# 06-USB3_PCIe.net
KiCad netlist of a schematic drawn in Altium Designer
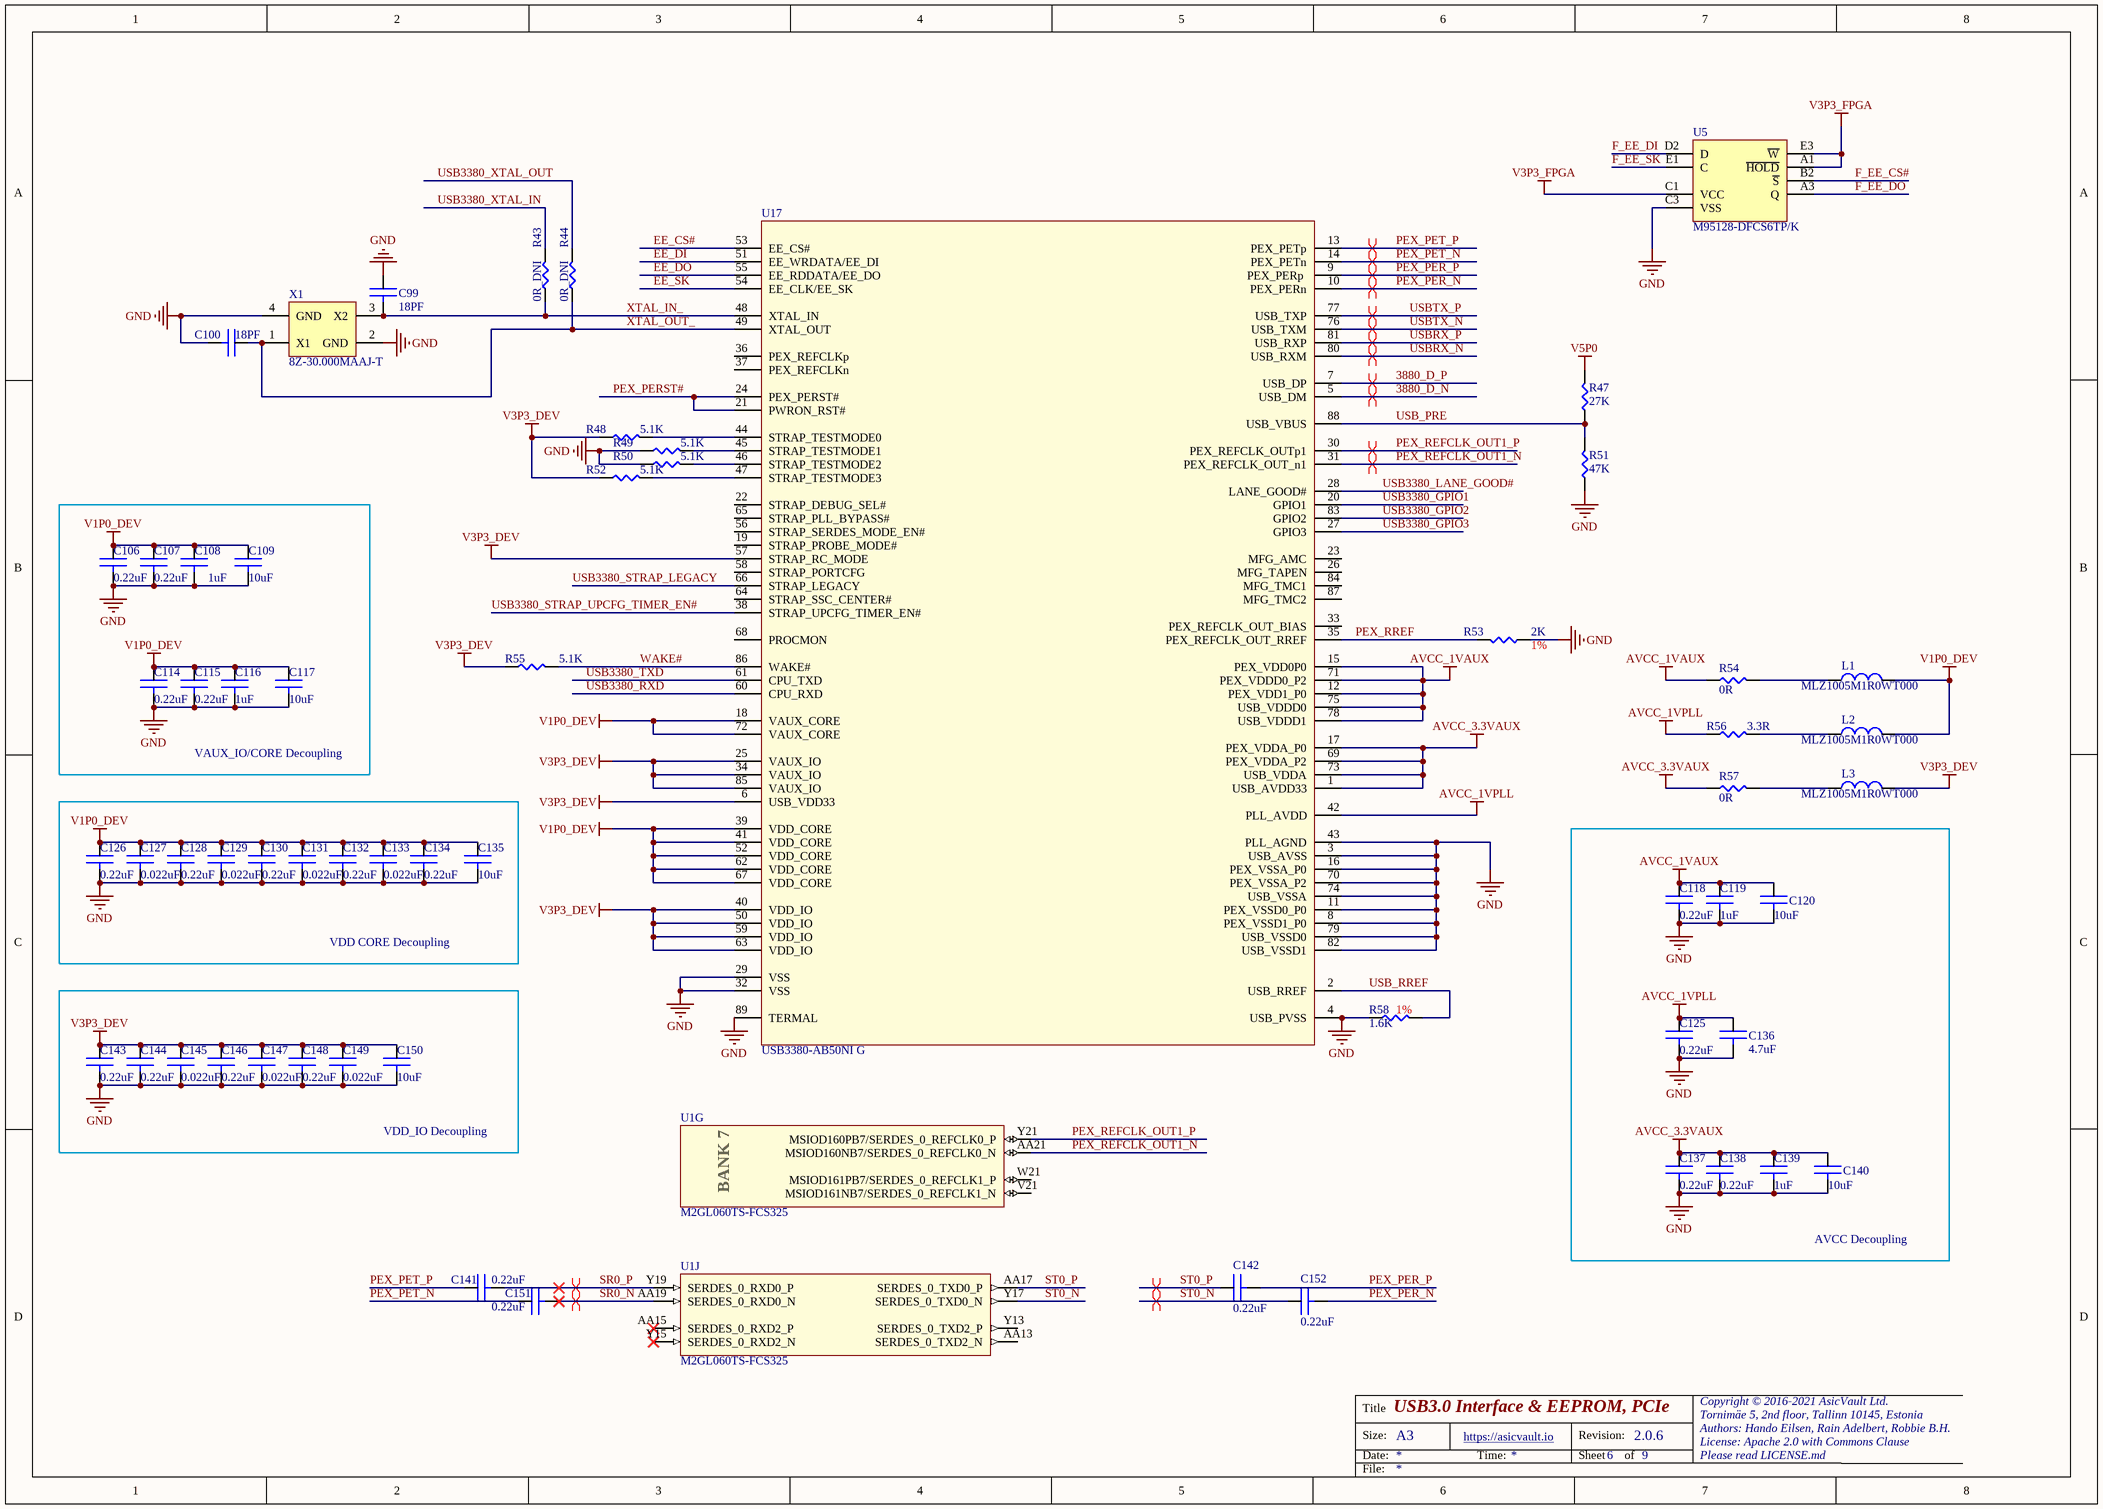
[diagram p0: 06-USB3_PCIe.SchDoc]

(export (version "E")
  (design (tool "Eeschema 10.0.6"))
  (components
    (comp (ref "C99") (value "18PF") (footprint "C0201") (libsource (lib "AMOLED") (part "18PF/0201")))
    (comp (ref "C100") (value "18PF") (footprint "C0201") (libsource (lib "AMOLED") (part "18PF/0201")))
    (comp (ref "C106") (value "0.22uF") (footprint "C0201") (libsource (lib "AMOLED") (part "0.22uF/0201")))
    (comp (ref "C107") (value "0.22uF") (footprint "C0201") (libsource (lib "AMOLED") (part "0.22uF/0201")))
    (comp (ref "C108")
      (value "1uF")
      (footprint "C0201")
      (libsource (lib "AMOLED") (part "1uF/0201/CC0201KRX7R7BB103"))
    )
    (comp (ref "C109") (value "10uF") (footprint "C0402") (libsource (lib "AMOLED") (part "10uF/0402")))
    (comp (ref "C114") (value "0.22uF") (footprint "C0201") (libsource (lib "AMOLED") (part "0.22uF/0201")))
    (comp (ref "C115") (value "0.22uF") (footprint "C0201") (libsource (lib "AMOLED") (part "0.22uF/0201")))
    (comp (ref "C116")
      (value "1uF")
      (footprint "C0201")
      (libsource (lib "AMOLED") (part "1uF/0201/CC0201KRX7R7BB103"))
    )
    (comp (ref "C117") (value "10uF") (footprint "C0402") (libsource (lib "AMOLED") (part "10uF/0402")))
    (comp (ref "C118") (value "0.22uF") (footprint "C0201") (libsource (lib "AMOLED") (part "0.22uF/0201")))
    (comp (ref "C119")
      (value "1uF")
      (footprint "C0201")
      (libsource (lib "AMOLED") (part "1uF/0201/CC0201KRX7R7BB103"))
    )
    (comp (ref "C120") (value "10uF") (footprint "C0402") (libsource (lib "AMOLED") (part "10uF/0402")))
    (comp (ref "C125") (value "0.22uF") (footprint "C0201") (libsource (lib "AMOLED") (part "0.22uF/0201")))
    (comp (ref "C126") (value "0.22uF") (footprint "C0201") (libsource (lib "AMOLED") (part "0.22uF/0201")))
    (comp (ref "C127") (value "0.022uF") (footprint "C0201") (libsource (lib "AMOLED") (part "0.022uF/0201")))
    (comp (ref "C128") (value "0.22uF") (footprint "C0201") (libsource (lib "AMOLED") (part "0.22uF/0201")))
    (comp (ref "C129") (value "0.022uF") (footprint "C0201") (libsource (lib "AMOLED") (part "0.022uF/0201")))
    (comp (ref "C130") (value "0.22uF") (footprint "C0201") (libsource (lib "AMOLED") (part "0.22uF/0201")))
    (comp (ref "C131") (value "0.022uF") (footprint "C0201") (libsource (lib "AMOLED") (part "0.022uF/0201")))
    (comp (ref "C132") (value "0.22uF") (footprint "C0201") (libsource (lib "AMOLED") (part "0.22uF/0201")))
    (comp (ref "C133") (value "0.022uF") (footprint "C0201") (libsource (lib "AMOLED") (part "0.022uF/0201")))
    (comp (ref "C134") (value "0.22uF") (footprint "C0201") (libsource (lib "AMOLED") (part "0.22uF/0201")))
    (comp (ref "C135") (value "10uF") (footprint "C0402") (libsource (lib "AMOLED") (part "10uF/0402")))
    (comp (ref "C136") (value "4.7uF") (footprint "C0201") (libsource (lib "AMOLED") (part "4.7uF/0201")))
    (comp (ref "C137") (value "0.22uF") (footprint "C0201") (libsource (lib "AMOLED") (part "0.22uF/0201")))
    (comp (ref "C138") (value "0.22uF") (footprint "C0201") (libsource (lib "AMOLED") (part "0.22uF/0201")))
    (comp (ref "C139")
      (value "1uF")
      (footprint "C0201")
      (libsource (lib "AMOLED") (part "1uF/0201/CC0201KRX7R7BB103"))
    )
    (comp (ref "C140") (value "10uF") (footprint "C0402") (libsource (lib "AMOLED") (part "10uF/0402")))
    (comp (ref "C141") (value "0.22uF") (footprint "C0201") (libsource (lib "AMOLED") (part "0.22uF/0201")))
    (comp (ref "C142") (value "0.22uF") (footprint "C0201") (libsource (lib "AMOLED") (part "0.22uF/0201")))
    (comp (ref "C143") (value "0.22uF") (footprint "C0201") (libsource (lib "AMOLED") (part "0.22uF/0201")))
    (comp (ref "C144") (value "0.22uF") (footprint "C0201") (libsource (lib "AMOLED") (part "0.22uF/0201")))
    (comp (ref "C145") (value "0.022uF") (footprint "C0201") (libsource (lib "AMOLED") (part "0.022uF/0201")))
    (comp (ref "C146") (value "0.22uF") (footprint "C0201") (libsource (lib "AMOLED") (part "0.22uF/0201")))
    (comp (ref "C147") (value "0.022uF") (footprint "C0201") (libsource (lib "AMOLED") (part "0.022uF/0201")))
    (comp (ref "C148") (value "0.22uF") (footprint "C0201") (libsource (lib "AMOLED") (part "0.22uF/0201")))
    (comp (ref "C149") (value "0.022uF") (footprint "C0201") (libsource (lib "AMOLED") (part "0.022uF/0201")))
    (comp (ref "C150") (value "10uF") (footprint "C0402") (libsource (lib "AMOLED") (part "10uF/0402")))
    (comp (ref "C151") (value "0.22uF") (footprint "C0201") (libsource (lib "AMOLED") (part "0.22uF/0201")))
    (comp (ref "C152") (value "0.22uF") (footprint "C0201") (libsource (lib "AMOLED") (part "0.22uF/0201")))
    (comp (ref "L1")
      (value "MLZ1005M1R0WT000")
      (footprint "L0402")
      (libsource (lib "AMOLED") (part "1uH/MLZ1005M1R0WT000"))
    )
    (comp (ref "L2")
      (value "MLZ1005M1R0WT000")
      (footprint "L0402")
      (libsource (lib "AMOLED") (part "1uH/MLZ1005M1R0WT000"))
    )
    (comp (ref "L3")
      (value "MLZ1005M1R0WT000")
      (footprint "L0402")
      (libsource (lib "AMOLED") (part "1uH/MLZ1005M1R0WT000"))
    )
    (comp (ref "R43") (value "0R_DNI") (footprint "R0201") (libsource (lib "Control_Board") (part "0R/0201")))
    (comp (ref "R44") (value "0R_DNI") (footprint "R0201") (libsource (lib "Control_Board") (part "0R/0201")))
    (comp (ref "R47")
      (value "27K")
      (footprint "R0201")
      (libsource (lib "Control_Board") (part "27K/1%/0201"))
    )
    (comp (ref "R48")
      (value "5.1K")
      (footprint "R0201")
      (libsource (lib "Control_Board") (part "5.1K/1%/0201"))
    )
    (comp (ref "R49")
      (value "5.1K")
      (footprint "R0201")
      (libsource (lib "Control_Board") (part "5.1K/1%/0201"))
    )
    (comp (ref "R50")
      (value "5.1K")
      (footprint "R0201")
      (libsource (lib "Control_Board") (part "5.1K/1%/0201"))
    )
    (comp (ref "R51")
      (value "47K")
      (footprint "R0201")
      (libsource (lib "Control_Board") (part "47K/1%/0201"))
    )
    (comp (ref "R52")
      (value "5.1K")
      (footprint "R0201")
      (libsource (lib "Control_Board") (part "5.1K/1%/0201"))
    )
    (comp (ref "R53") (value "2K") (footprint "R0201") (libsource (lib "Control_Board") (part "2K/1%/0201")))
    (comp (ref "R54") (value "0R") (footprint "R0201") (libsource (lib "Board3") (part "0R/0201")))
    (comp (ref "R55")
      (value "5.1K")
      (footprint "R0201")
      (libsource (lib "Control_Board") (part "5.1K/1%/0201"))
    )
    (comp (ref "R56")
      (value "3.3R")
      (footprint "R0201")
      (libsource (lib "Control_Board") (part "3.3R/1%/0201"))
    )
    (comp (ref "R57") (value "0R") (footprint "R0201") (libsource (lib "Board3") (part "0R/0201")))
    (comp (ref "R58")
      (value "1.6K")
      (footprint "R0201")
      (libsource (lib "Control_Board") (part "1.6K/1%/0201"))
    )
    (comp (ref "U1")
      (value "M2GL060TS-FCS325")
      (footprint "FCS325-OPT1")
      (libsource (lib "Board3") (part "M2GL060TS-FCS325"))
    )
    (comp (ref "U5")
      (value "M95128-DFCS6TP/K")
      (footprint "WLCSP8")
      (libsource (lib "AMOLED") (part "M95128-DFCS6TP/K"))
    )
    (comp (ref "U17")
      (value "USB3380-AB50NI G")
      (footprint "QFN88P")
      (libsource (lib "AMOLED") (part "USB3380-AB50NI G"))
    )
    (comp (ref "X1")
      (value "8Z-30.000MAAJ-T")
      (footprint "2520")
      (libsource (lib "AMOLED") (part "8Z-30.000MAAJ-T"))
    )
  )
  (nets
    (net (code "1") (name "/3880_D_N") (class "Default")
      (node (ref "U17") (pin "5") (pinfunction "USB_DM_5") (pintype "passive"))
    )
    (net (code "2") (name "/3880_D_P") (class "Default")
      (node (ref "U17") (pin "7") (pinfunction "USB_DP_7") (pintype "passive"))
    )
    (net (code "3") (name "/EE_CS#") (class "Default")
      (node (ref "U17") (pin "53") (pinfunction "EE_CS#_53") (pintype "passive"))
    )
    (net (code "4") (name "/EE_DI") (class "Default")
      (node (ref "U17") (pin "51") (pinfunction "EE_WRDATA/EE_DI_51") (pintype "passive"))
    )
    (net (code "5") (name "/EE_DO") (class "Default")
      (node (ref "U17") (pin "55") (pinfunction "EE_RDDATA/EE_DO_55") (pintype "passive"))
    )
    (net (code "6") (name "/EE_SK") (class "Default")
      (node (ref "U17") (pin "54") (pinfunction "EE_CLK/EE_SK_54") (pintype "passive"))
    )
    (net (code "7") (name "/F_EE_CS#") (class "Default")
      (node (ref "U5") (pin "B2") (pinfunction "~{S}_B2") (pintype "passive"))
    )
    (net (code "8") (name "/F_EE_DI") (class "Default")
      (node (ref "U5") (pin "D2") (pinfunction "D_D2") (pintype "passive"))
    )
    (net (code "9") (name "/F_EE_DO") (class "Default")
      (node (ref "U5") (pin "A3") (pinfunction "Q_A3") (pintype "passive"))
    )
    (net (code "10") (name "/F_EE_SK") (class "Default")
      (node (ref "U5") (pin "E1") (pinfunction "C_E1") (pintype "passive"))
    )
    (net (code "11") (name "/PEX_PERST#") (class "Default")
      (node (ref "U17") (pin "21") (pinfunction "PWRON_RST#_21") (pintype "passive"))
      (node (ref "U17") (pin "24") (pinfunction "PEX_PERST#_24") (pintype "passive"))
    )
    (net (code "12") (name "/PEX_PER_N") (class "Default")
      (node (ref "C152") (pin "2") (pinfunction "2_2") (pintype "passive"))
      (node (ref "U17") (pin "10") (pinfunction "PEX_PERn_10") (pintype "passive"))
    )
    (net (code "13") (name "/PEX_PER_P") (class "Default")
      (node (ref "C142") (pin "2") (pinfunction "2_2") (pintype "passive"))
      (node (ref "U17") (pin "9") (pinfunction "PEX_PERp_9") (pintype "passive"))
    )
    (net (code "14") (name "/PEX_PET_N") (class "Default")
      (node (ref "C151") (pin "1") (pinfunction "1_1") (pintype "passive"))
      (node (ref "U17") (pin "14") (pinfunction "PEX_PETn_14") (pintype "passive"))
    )
    (net (code "15") (name "/PEX_PET_P") (class "Default")
      (node (ref "C141") (pin "1") (pinfunction "1_1") (pintype "passive"))
      (node (ref "U17") (pin "13") (pinfunction "PEX_PETp_13") (pintype "passive"))
    )
    (net (code "16") (name "/PEX_REFCLK_OUT1_N") (class "Default")
      (node (ref "U1") (pin "AA21") (pinfunction "MSIOD160NB7/SERDES_0_REFCLK0_N_AA21") (pintype "bidirectional"))
      (node (ref "U17") (pin "31") (pinfunction "PEX_REFCLK_OUT_n1_31") (pintype "passive"))
    )
    (net (code "17") (name "/PEX_REFCLK_OUT1_P") (class "Default")
      (node (ref "U1") (pin "Y21") (pinfunction "MSIOD160PB7/SERDES_0_REFCLK0_P_Y21") (pintype "bidirectional"))
      (node (ref "U17") (pin "30") (pinfunction "PEX_REFCLK_OUTp1_30") (pintype "passive"))
    )
    (net (code "18") (name "/PEX_RREF") (class "Default")
      (node (ref "R53") (pin "2") (pinfunction "2_2") (pintype "passive"))
      (node (ref "U17") (pin "35") (pinfunction "PEX_REFCLK_OUT_RREF_35") (pintype "passive"))
    )
    (net (code "19") (name "/SR0_N") (class "Default")
      (node (ref "C151") (pin "2") (pinfunction "2_2") (pintype "passive"))
      (node (ref "U1") (pin "AA19") (pinfunction "SERDES_0_RXD0_N_AA19") (pintype "input"))
    )
    (net (code "20") (name "/SR0_P") (class "Default")
      (node (ref "C141") (pin "2") (pinfunction "2_2") (pintype "passive"))
      (node (ref "U1") (pin "Y19") (pinfunction "SERDES_0_RXD0_P_Y19") (pintype "input"))
    )
    (net (code "21") (name "/ST0_N") (class "Default")
      (node (ref "C152") (pin "1") (pinfunction "1_1") (pintype "passive"))
      (node (ref "U1") (pin "Y17") (pinfunction "SERDES_0_TXD0_N_Y17") (pintype "output"))
    )
    (net (code "22") (name "/ST0_P") (class "Default")
      (node (ref "C142") (pin "1") (pinfunction "1_1") (pintype "passive"))
      (node (ref "U1") (pin "AA17") (pinfunction "SERDES_0_TXD0_P_AA17") (pintype "output"))
    )
    (net (code "23") (name "/USB3380_GPIO1") (class "Default")
      (node (ref "U17") (pin "20") (pinfunction "GPIO1_20") (pintype "passive"))
    )
    (net (code "24") (name "/USB3380_GPIO2") (class "Default")
      (node (ref "U17") (pin "83") (pinfunction "GPIO2_83") (pintype "passive"))
    )
    (net (code "25") (name "/USB3380_GPIO3") (class "Default")
      (node (ref "U17") (pin "27") (pinfunction "GPIO3_27") (pintype "passive"))
    )
    (net (code "26") (name "/USB3380_LANE_GOOD#") (class "Default")
      (node (ref "U17") (pin "28") (pinfunction "LANE_GOOD#_28") (pintype "passive"))
    )
    (net (code "27") (name "/USB3380_RXD") (class "Default")
      (node (ref "U17") (pin "60") (pinfunction "CPU_RXD_60") (pintype "passive"))
    )
    (net (code "28") (name "/USB3380_STRAP_LEGACY") (class "Default")
      (node (ref "U17") (pin "66") (pinfunction "STRAP_LEGACY_66") (pintype "passive"))
    )
    (net (code "29") (name "/USB3380_STRAP_UPCFG_TIMER_EN#") (class "Default")
      (node (ref "U17") (pin "38") (pinfunction "STRAP_UPCFG_TIMER_EN#_38") (pintype "passive"))
    )
    (net (code "30") (name "/USB3380_TXD") (class "Default")
      (node (ref "U17") (pin "61") (pinfunction "CPU_TXD_61") (pintype "passive"))
    )
    (net (code "31") (name "/USB3380_XTAL_IN") (class "Default")
      (node (ref "R43") (pin "2") (pinfunction "2_2") (pintype "passive"))
    )
    (net (code "32") (name "/USB3380_XTAL_OUT") (class "Default")
      (node (ref "R44") (pin "2") (pinfunction "2_2") (pintype "passive"))
    )
    (net (code "33") (name "/USBRX_N") (class "Default")
      (node (ref "U17") (pin "80") (pinfunction "USB_RXM_80") (pintype "passive"))
    )
    (net (code "34") (name "/USBRX_P") (class "Default")
      (node (ref "U17") (pin "81") (pinfunction "USB_RXP_81") (pintype "passive"))
    )
    (net (code "35") (name "/USBTX_N") (class "Default")
      (node (ref "U17") (pin "76") (pinfunction "USB_TXM_76") (pintype "passive"))
    )
    (net (code "36") (name "/USBTX_P") (class "Default")
      (node (ref "U17") (pin "77") (pinfunction "USB_TXP_77") (pintype "passive"))
    )
    (net (code "37") (name "/USB_PRE") (class "Default")
      (node (ref "R47") (pin "1") (pinfunction "1_1") (pintype "passive"))
      (node (ref "R51") (pin "2") (pinfunction "2_2") (pintype "passive"))
      (node (ref "U17") (pin "88") (pinfunction "USB_VBUS_88") (pintype "passive"))
    )
    (net (code "38") (name "/USB_RREF") (class "Default")
      (node (ref "R58") (pin "2") (pinfunction "2_2") (pintype "passive"))
      (node (ref "U17") (pin "2") (pinfunction "USB_RREF_2") (pintype "passive"))
    )
    (net (code "39") (name "/WAKE#") (class "Default")
      (node (ref "R55") (pin "2") (pinfunction "2_2") (pintype "passive"))
      (node (ref "U17") (pin "86") (pinfunction "WAKE#_86") (pintype "passive"))
    )
    (net (code "40") (name "/XTAL_IN_") (class "Default")
      (node (ref "C99") (pin "2") (pinfunction "2_2") (pintype "passive"))
      (node (ref "R43") (pin "1") (pinfunction "1_1") (pintype "passive"))
      (node (ref "U17") (pin "48") (pinfunction "XTAL_IN_48") (pintype "passive"))
      (node (ref "X1") (pin "3") (pinfunction "X2_3") (pintype "passive"))
    )
    (net (code "41") (name "/XTAL_OUT_") (class "Default")
      (node (ref "C100") (pin "1") (pinfunction "1_1") (pintype "passive"))
      (node (ref "R44") (pin "1") (pinfunction "1_1") (pintype "passive"))
      (node (ref "U17") (pin "49") (pinfunction "XTAL_OUT_49") (pintype "passive"))
      (node (ref "X1") (pin "1") (pinfunction "X1_1") (pintype "passive"))
    )
    (net (code "42") (name "AVCC_1VAUX") (class "Default")
      (node (ref "C118") (pin "1") (pinfunction "1_1") (pintype "passive"))
      (node (ref "C119") (pin "1") (pinfunction "1_1") (pintype "passive"))
      (node (ref "C120") (pin "1") (pinfunction "1_1") (pintype "passive"))
      (node (ref "R54") (pin "1") (pinfunction "1_1") (pintype "passive"))
      (node (ref "U17") (pin "12") (pinfunction "PEX_VDD1_P0_12") (pintype "passive"))
      (node (ref "U17") (pin "15") (pinfunction "PEX_VDD0P0_15") (pintype "passive"))
      (node (ref "U17") (pin "71") (pinfunction "PEX_VDDD0_P2_71") (pintype "passive"))
      (node (ref "U17") (pin "75") (pinfunction "USB_VDDD0_75") (pintype "passive"))
      (node (ref "U17") (pin "78") (pinfunction "USB_VDDD1_78") (pintype "passive"))
    )
    (net (code "43") (name "AVCC_1VPLL") (class "Default")
      (node (ref "C125") (pin "1") (pinfunction "1_1") (pintype "passive"))
      (node (ref "C136") (pin "1") (pinfunction "1_1") (pintype "passive"))
      (node (ref "R56") (pin "1") (pinfunction "1_1") (pintype "passive"))
      (node (ref "U17") (pin "42") (pinfunction "PLL_AVDD_42") (pintype "passive"))
    )
    (net (code "44") (name "AVCC_3.3VAUX") (class "Default")
      (node (ref "C137") (pin "1") (pinfunction "1_1") (pintype "passive"))
      (node (ref "C138") (pin "1") (pinfunction "1_1") (pintype "passive"))
      (node (ref "C139") (pin "1") (pinfunction "1_1") (pintype "passive"))
      (node (ref "C140") (pin "1") (pinfunction "1_1") (pintype "passive"))
      (node (ref "R57") (pin "1") (pinfunction "1_1") (pintype "passive"))
      (node (ref "U17") (pin "1") (pinfunction "USB_AVDD33_1") (pintype "passive"))
      (node (ref "U17") (pin "17") (pinfunction "PEX_VDDA_P0_17") (pintype "passive"))
      (node (ref "U17") (pin "69") (pinfunction "PEX_VDDA_P2_69") (pintype "passive"))
      (node (ref "U17") (pin "73") (pinfunction "USB_VDDA_73") (pintype "passive"))
    )
    (net (code "45") (name "GND") (class "Default")
      (node (ref "C100") (pin "2") (pinfunction "2_2") (pintype "passive"))
      (node (ref "C106") (pin "2") (pinfunction "2_2") (pintype "passive"))
      (node (ref "C107") (pin "2") (pinfunction "2_2") (pintype "passive"))
      (node (ref "C108") (pin "2") (pinfunction "2_2") (pintype "passive"))
      (node (ref "C109") (pin "2") (pinfunction "2_2") (pintype "passive"))
      (node (ref "C114") (pin "2") (pinfunction "2_2") (pintype "passive"))
      (node (ref "C115") (pin "2") (pinfunction "2_2") (pintype "passive"))
      (node (ref "C116") (pin "2") (pinfunction "2_2") (pintype "passive"))
      (node (ref "C117") (pin "2") (pinfunction "2_2") (pintype "passive"))
      (node (ref "C118") (pin "2") (pinfunction "2_2") (pintype "passive"))
      (node (ref "C119") (pin "2") (pinfunction "2_2") (pintype "passive"))
      (node (ref "C120") (pin "2") (pinfunction "2_2") (pintype "passive"))
      (node (ref "C125") (pin "2") (pinfunction "2_2") (pintype "passive"))
      (node (ref "C126") (pin "2") (pinfunction "2_2") (pintype "passive"))
      (node (ref "C127") (pin "2") (pinfunction "2_2") (pintype "passive"))
      (node (ref "C128") (pin "2") (pinfunction "2_2") (pintype "passive"))
      (node (ref "C129") (pin "2") (pinfunction "2_2") (pintype "passive"))
      (node (ref "C130") (pin "2") (pinfunction "2_2") (pintype "passive"))
      (node (ref "C131") (pin "2") (pinfunction "2_2") (pintype "passive"))
      (node (ref "C132") (pin "2") (pinfunction "2_2") (pintype "passive"))
      (node (ref "C133") (pin "2") (pinfunction "2_2") (pintype "passive"))
      (node (ref "C134") (pin "2") (pinfunction "2_2") (pintype "passive"))
      (node (ref "C135") (pin "2") (pinfunction "2_2") (pintype "passive"))
      (node (ref "C136") (pin "2") (pinfunction "2_2") (pintype "passive"))
      (node (ref "C137") (pin "2") (pinfunction "2_2") (pintype "passive"))
      (node (ref "C138") (pin "2") (pinfunction "2_2") (pintype "passive"))
      (node (ref "C139") (pin "2") (pinfunction "2_2") (pintype "passive"))
      (node (ref "C140") (pin "2") (pinfunction "2_2") (pintype "passive"))
      (node (ref "C143") (pin "2") (pinfunction "2_2") (pintype "passive"))
      (node (ref "C144") (pin "2") (pinfunction "2_2") (pintype "passive"))
      (node (ref "C145") (pin "2") (pinfunction "2_2") (pintype "passive"))
      (node (ref "C146") (pin "2") (pinfunction "2_2") (pintype "passive"))
      (node (ref "C147") (pin "2") (pinfunction "2_2") (pintype "passive"))
      (node (ref "C148") (pin "2") (pinfunction "2_2") (pintype "passive"))
      (node (ref "C149") (pin "2") (pinfunction "2_2") (pintype "passive"))
      (node (ref "C150") (pin "2") (pinfunction "2_2") (pintype "passive"))
      (node (ref "C99") (pin "1") (pinfunction "1_1") (pintype "passive"))
      (node (ref "R49") (pin "1") (pinfunction "1_1") (pintype "passive"))
      (node (ref "R50") (pin "1") (pinfunction "1_1") (pintype "passive"))
      (node (ref "R51") (pin "1") (pinfunction "1_1") (pintype "passive"))
      (node (ref "R53") (pin "1") (pinfunction "1_1") (pintype "passive"))
      (node (ref "R58") (pin "1") (pinfunction "1_1") (pintype "passive"))
      (node (ref "U17") (pin "11") (pinfunction "PEX_VSSD0_P0_11") (pintype "passive"))
      (node (ref "U17") (pin "16") (pinfunction "PEX_VSSA_P0_16") (pintype "passive"))
      (node (ref "U17") (pin "29") (pinfunction "VSS_29") (pintype "passive"))
      (node (ref "U17") (pin "3") (pinfunction "USB_AVSS_3") (pintype "passive"))
      (node (ref "U17") (pin "32") (pinfunction "VSS_32") (pintype "passive"))
      (node (ref "U17") (pin "4") (pinfunction "USB_PVSS_4") (pintype "passive"))
      (node (ref "U17") (pin "43") (pinfunction "PLL_AGND_43") (pintype "passive"))
      (node (ref "U17") (pin "70") (pinfunction "PEX_VSSA_P2_70") (pintype "passive"))
      (node (ref "U17") (pin "74") (pinfunction "USB_VSSA_74") (pintype "passive"))
      (node (ref "U17") (pin "79") (pinfunction "USB_VSSD0_79") (pintype "passive"))
      (node (ref "U17") (pin "8") (pinfunction "PEX_VSSD1_P0_8") (pintype "passive"))
      (node (ref "U17") (pin "82") (pinfunction "USB_VSSD1_82") (pintype "passive"))
      (node (ref "U17") (pin "89") (pinfunction "TERMAL_89") (pintype "passive"))
      (node (ref "U5") (pin "C3") (pinfunction "VSS_C3") (pintype "passive"))
      (node (ref "X1") (pin "2") (pinfunction "GND_2") (pintype "passive"))
      (node (ref "X1") (pin "4") (pinfunction "GND_4") (pintype "passive"))
    )
    (net (code "46") (name "Net-(L1-Pad1)") (class "Default")
      (node (ref "L1") (pin "1") (pinfunction "1_1") (pintype "passive"))
      (node (ref "R54") (pin "2") (pinfunction "2_2") (pintype "passive"))
    )
    (net (code "47") (name "Net-(L2-Pad1)") (class "Default")
      (node (ref "L2") (pin "1") (pinfunction "1_1") (pintype "passive"))
      (node (ref "R56") (pin "2") (pinfunction "2_2") (pintype "passive"))
    )
    (net (code "48") (name "Net-(L3-Pad1)") (class "Default")
      (node (ref "L3") (pin "1") (pinfunction "1_1") (pintype "passive"))
      (node (ref "R57") (pin "2") (pinfunction "2_2") (pintype "passive"))
    )
    (net (code "49") (name "Net-(U17-STRAP_TESTMODE0)") (class "Default")
      (node (ref "R48") (pin "2") (pinfunction "2_2") (pintype "passive"))
      (node (ref "U17") (pin "44") (pinfunction "STRAP_TESTMODE0_44") (pintype "passive"))
    )
    (net (code "50") (name "Net-(U17-STRAP_TESTMODE1)") (class "Default")
      (node (ref "R49") (pin "2") (pinfunction "2_2") (pintype "passive"))
      (node (ref "U17") (pin "45") (pinfunction "STRAP_TESTMODE1_45") (pintype "passive"))
    )
    (net (code "51") (name "Net-(U17-STRAP_TESTMODE2)") (class "Default")
      (node (ref "R50") (pin "2") (pinfunction "2_2") (pintype "passive"))
      (node (ref "U17") (pin "46") (pinfunction "STRAP_TESTMODE2_46") (pintype "passive"))
    )
    (net (code "52") (name "Net-(U17-STRAP_TESTMODE3)") (class "Default")
      (node (ref "R52") (pin "2") (pinfunction "2_2") (pintype "passive"))
      (node (ref "U17") (pin "47") (pinfunction "STRAP_TESTMODE3_47") (pintype "passive"))
    )
    (net (code "53") (name "V1P0_DEV") (class "Default")
      (node (ref "C106") (pin "1") (pinfunction "1_1") (pintype "passive"))
      (node (ref "C107") (pin "1") (pinfunction "1_1") (pintype "passive"))
      (node (ref "C108") (pin "1") (pinfunction "1_1") (pintype "passive"))
      (node (ref "C109") (pin "1") (pinfunction "1_1") (pintype "passive"))
      (node (ref "C114") (pin "1") (pinfunction "1_1") (pintype "passive"))
      (node (ref "C115") (pin "1") (pinfunction "1_1") (pintype "passive"))
      (node (ref "C116") (pin "1") (pinfunction "1_1") (pintype "passive"))
      (node (ref "C117") (pin "1") (pinfunction "1_1") (pintype "passive"))
      (node (ref "C126") (pin "1") (pinfunction "1_1") (pintype "passive"))
      (node (ref "C127") (pin "1") (pinfunction "1_1") (pintype "passive"))
      (node (ref "C128") (pin "1") (pinfunction "1_1") (pintype "passive"))
      (node (ref "C129") (pin "1") (pinfunction "1_1") (pintype "passive"))
      (node (ref "C130") (pin "1") (pinfunction "1_1") (pintype "passive"))
      (node (ref "C131") (pin "1") (pinfunction "1_1") (pintype "passive"))
      (node (ref "C132") (pin "1") (pinfunction "1_1") (pintype "passive"))
      (node (ref "C133") (pin "1") (pinfunction "1_1") (pintype "passive"))
      (node (ref "C134") (pin "1") (pinfunction "1_1") (pintype "passive"))
      (node (ref "C135") (pin "1") (pinfunction "1_1") (pintype "passive"))
      (node (ref "L1") (pin "2") (pinfunction "2_2") (pintype "passive"))
      (node (ref "L2") (pin "2") (pinfunction "2_2") (pintype "passive"))
      (node (ref "U17") (pin "18") (pinfunction "VAUX_CORE_18") (pintype "passive"))
      (node (ref "U17") (pin "39") (pinfunction "VDD_CORE_39") (pintype "passive"))
      (node (ref "U17") (pin "41") (pinfunction "VDD_CORE_41") (pintype "passive"))
      (node (ref "U17") (pin "52") (pinfunction "VDD_CORE_52") (pintype "passive"))
      (node (ref "U17") (pin "62") (pinfunction "VDD_CORE_62") (pintype "passive"))
      (node (ref "U17") (pin "67") (pinfunction "VDD_CORE_67") (pintype "passive"))
      (node (ref "U17") (pin "72") (pinfunction "VAUX_CORE_72") (pintype "passive"))
    )
    (net (code "54") (name "V3P3_DEV") (class "Default")
      (node (ref "C143") (pin "1") (pinfunction "1_1") (pintype "passive"))
      (node (ref "C144") (pin "1") (pinfunction "1_1") (pintype "passive"))
      (node (ref "C145") (pin "1") (pinfunction "1_1") (pintype "passive"))
      (node (ref "C146") (pin "1") (pinfunction "1_1") (pintype "passive"))
      (node (ref "C147") (pin "1") (pinfunction "1_1") (pintype "passive"))
      (node (ref "C148") (pin "1") (pinfunction "1_1") (pintype "passive"))
      (node (ref "C149") (pin "1") (pinfunction "1_1") (pintype "passive"))
      (node (ref "C150") (pin "1") (pinfunction "1_1") (pintype "passive"))
      (node (ref "L3") (pin "2") (pinfunction "2_2") (pintype "passive"))
      (node (ref "R48") (pin "1") (pinfunction "1_1") (pintype "passive"))
      (node (ref "R52") (pin "1") (pinfunction "1_1") (pintype "passive"))
      (node (ref "R55") (pin "1") (pinfunction "1_1") (pintype "passive"))
      (node (ref "U17") (pin "25") (pinfunction "VAUX_IO_25") (pintype "passive"))
      (node (ref "U17") (pin "34") (pinfunction "VAUX_IO_34") (pintype "passive"))
      (node (ref "U17") (pin "40") (pinfunction "VDD_IO_40") (pintype "passive"))
      (node (ref "U17") (pin "50") (pinfunction "VDD_IO_50") (pintype "passive"))
      (node (ref "U17") (pin "57") (pinfunction "STRAP_RC_MODE_57") (pintype "passive"))
      (node (ref "U17") (pin "59") (pinfunction "VDD_IO_59") (pintype "passive"))
      (node (ref "U17") (pin "6") (pinfunction "USB_VDD33_6") (pintype "passive"))
      (node (ref "U17") (pin "63") (pinfunction "VDD_IO_63") (pintype "passive"))
      (node (ref "U17") (pin "85") (pinfunction "VAUX_IO_85") (pintype "passive"))
    )
    (net (code "55") (name "V3P3_FPGA") (class "Default")
      (node (ref "U5") (pin "A1") (pinfunction "~{HOLD}_A1") (pintype "passive"))
      (node (ref "U5") (pin "C1") (pinfunction "VCC_C1") (pintype "passive"))
      (node (ref "U5") (pin "E3") (pinfunction "~{W}_E3") (pintype "passive"))
    )
    (net (code "56") (name "V5P0") (class "Default")
      (node (ref "R47") (pin "2") (pinfunction "2_2") (pintype "passive"))
    )
    (net (code "57") (name "unconnected-(U1G-MSIOD161NB7{slash}SERDES_0_REFCLK1_N-PadV21)") (class "Default")
      (node (ref "U1") (pin "V21") (pinfunction "MSIOD161NB7/SERDES_0_REFCLK1_N_V21") (pintype "bidirectional"))
    )
    (net (code "58") (name "unconnected-(U1G-MSIOD161PB7{slash}SERDES_0_REFCLK1_P-PadW21)") (class "Default")
      (node (ref "U1") (pin "W21") (pinfunction "MSIOD161PB7/SERDES_0_REFCLK1_P_W21") (pintype "bidirectional"))
    )
    (net (code "59") (name "unconnected-(U1J-SERDES_0_RXD2_N-PadY15)") (class "Default")
      (node (ref "U1") (pin "Y15") (pinfunction "SERDES_0_RXD2_N_Y15") (pintype "input+no_connect"))
    )
    (net (code "60") (name "unconnected-(U1J-SERDES_0_RXD2_P-PadAA15)") (class "Default")
      (node (ref "U1") (pin "AA15") (pinfunction "SERDES_0_RXD2_P_AA15") (pintype "input+no_connect"))
    )
    (net (code "61") (name "unconnected-(U1J-SERDES_0_TXD2_N-PadAA13)") (class "Default")
      (node (ref "U1") (pin "AA13") (pinfunction "SERDES_0_TXD2_N_AA13") (pintype "output"))
    )
    (net (code "62") (name "unconnected-(U1J-SERDES_0_TXD2_P-PadY13)") (class "Default")
      (node (ref "U1") (pin "Y13") (pinfunction "SERDES_0_TXD2_P_Y13") (pintype "output"))
    )
    (net (code "63") (name "unconnected-(U17-MFG_AMC-Pad23)") (class "Default")
      (node (ref "U17") (pin "23") (pinfunction "MFG_AMC_23") (pintype "passive"))
    )
    (net (code "64") (name "unconnected-(U17-MFG_TAPEN-Pad26)") (class "Default")
      (node (ref "U17") (pin "26") (pinfunction "MFG_TAPEN_26") (pintype "passive"))
    )
    (net (code "65") (name "unconnected-(U17-MFG_TMC1-Pad84)") (class "Default")
      (node (ref "U17") (pin "84") (pinfunction "MFG_TMC1_84") (pintype "passive"))
    )
    (net (code "66") (name "unconnected-(U17-MFG_TMC2-Pad87)") (class "Default")
      (node (ref "U17") (pin "87") (pinfunction "MFG_TMC2_87") (pintype "passive"))
    )
    (net (code "67") (name "unconnected-(U17-PEX_REFCLK_OUT_BIAS-Pad33)") (class "Default")
      (node (ref "U17") (pin "33") (pinfunction "PEX_REFCLK_OUT_BIAS_33") (pintype "passive"))
    )
    (net (code "68") (name "unconnected-(U17-PEX_REFCLKn-Pad37)") (class "Default")
      (node (ref "U17") (pin "37") (pinfunction "PEX_REFCLKn_37") (pintype "passive"))
    )
    (net (code "69") (name "unconnected-(U17-PEX_REFCLKp-Pad36)") (class "Default")
      (node (ref "U17") (pin "36") (pinfunction "PEX_REFCLKp_36") (pintype "passive"))
    )
    (net (code "70") (name "unconnected-(U17-PROCMON-Pad68)") (class "Default")
      (node (ref "U17") (pin "68") (pinfunction "PROCMON_68") (pintype "passive"))
    )
    (net (code "71") (name "unconnected-(U17-STRAP_DEBUG_SEL#-Pad22)") (class "Default")
      (node (ref "U17") (pin "22") (pinfunction "STRAP_DEBUG_SEL#_22") (pintype "passive"))
    )
    (net (code "72") (name "unconnected-(U17-STRAP_PLL_BYPASS#-Pad65)") (class "Default")
      (node (ref "U17") (pin "65") (pinfunction "STRAP_PLL_BYPASS#_65") (pintype "passive"))
    )
    (net (code "73") (name "unconnected-(U17-STRAP_PORTCFG-Pad58)") (class "Default")
      (node (ref "U17") (pin "58") (pinfunction "STRAP_PORTCFG_58") (pintype "passive"))
    )
    (net (code "74") (name "unconnected-(U17-STRAP_PROBE_MODE#-Pad19)") (class "Default")
      (node (ref "U17") (pin "19") (pinfunction "STRAP_PROBE_MODE#_19") (pintype "passive"))
    )
    (net (code "75") (name "unconnected-(U17-STRAP_SERDES_MODE_EN#-Pad56)") (class "Default")
      (node (ref "U17") (pin "56") (pinfunction "STRAP_SERDES_MODE_EN#_56") (pintype "passive"))
    )
    (net (code "76") (name "unconnected-(U17-STRAP_SSC_CENTER#-Pad64)") (class "Default")
      (node (ref "U17") (pin "64") (pinfunction "STRAP_SSC_CENTER#_64") (pintype "passive"))
    )
  )
)
